# neural_network.net
KiCad netlist of a schematic drawn in EAGLE
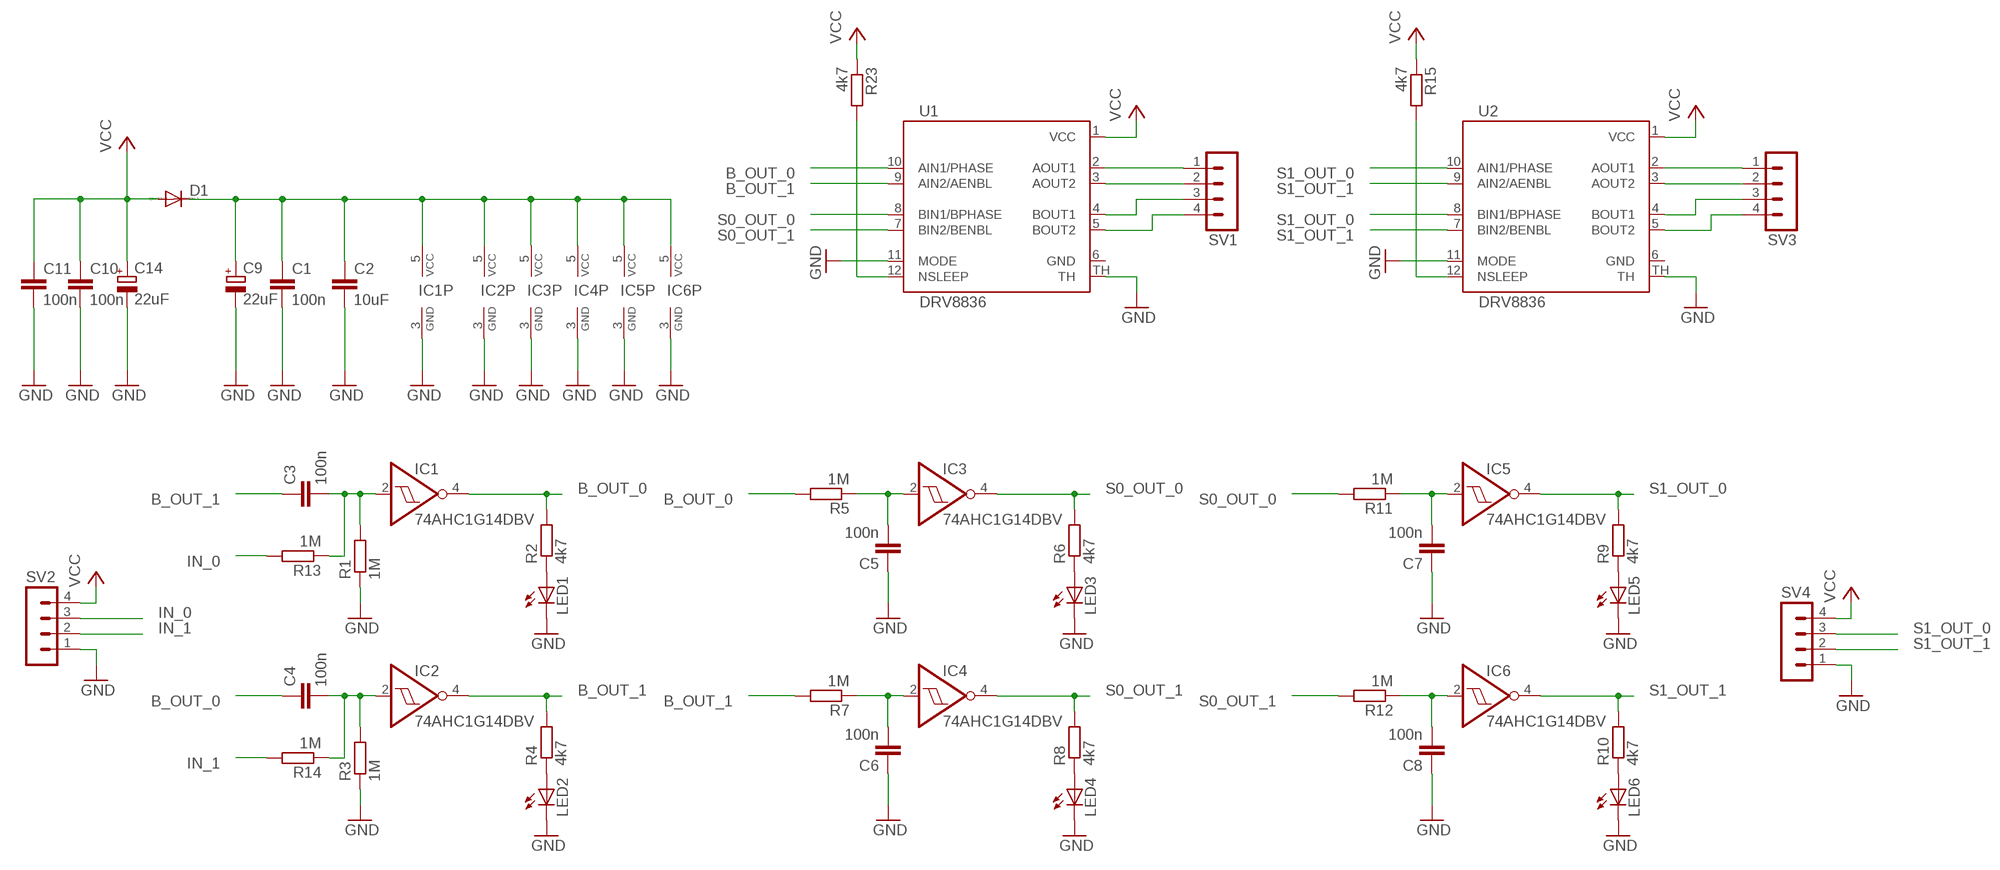
[diagram p0: schematic, sheet 1]

(export (version "E")
  (design (tool "Eeschema 10.0.6"))
  (components
    (comp (ref "C1")
      (value "100n")
      (footprint "eagle-import:C0805")
      (libsource (lib "eagle-import") (part "C-EUC0805"))
    )
    (comp (ref "C2")
      (value "10uF")
      (footprint "eagle-import:C0805")
      (libsource (lib "eagle-import") (part "C-EUC0805"))
    )
    (comp (ref "C3")
      (value "100n")
      (footprint "eagle-import:C0805")
      (libsource (lib "eagle-import") (part "C-EUC0805"))
    )
    (comp (ref "C4")
      (value "100n")
      (footprint "eagle-import:C0805")
      (libsource (lib "eagle-import") (part "C-EUC0805"))
    )
    (comp (ref "C5")
      (value "100n")
      (footprint "eagle-import:C0805")
      (libsource (lib "eagle-import") (part "C-EUC0805"))
    )
    (comp (ref "C6")
      (value "100n")
      (footprint "eagle-import:C0805")
      (libsource (lib "eagle-import") (part "C-EUC0805"))
    )
    (comp (ref "C7")
      (value "100n")
      (footprint "eagle-import:C0805")
      (libsource (lib "eagle-import") (part "C-EUC0805"))
    )
    (comp (ref "C8")
      (value "100n")
      (footprint "eagle-import:C0805")
      (libsource (lib "eagle-import") (part "C-EUC0805"))
    )
    (comp (ref "C9")
      (value "22uF")
      (footprint "eagle-import:153CLV-0605")
      (libsource (lib "eagle-import") (part "CPOL-EU153CLV-0605"))
    )
    (comp (ref "C10")
      (value "100n")
      (footprint "eagle-import:C0805")
      (libsource (lib "eagle-import") (part "C-EUC0805"))
    )
    (comp (ref "C11")
      (value "100n")
      (footprint "eagle-import:C0805")
      (libsource (lib "eagle-import") (part "C-EUC0805"))
    )
    (comp (ref "C14")
      (value "22uF")
      (footprint "eagle-import:153CLV-0605")
      (libsource (lib "eagle-import") (part "CPOL-EU153CLV-0605"))
    )
    (comp (ref "D1")
      (value "DIODE-DO214AA")
      (footprint "eagle-import:DO214AA")
      (libsource (lib "eagle-import") (part "DIODE-DO214AA"))
    )
    (comp (ref "IC1")
      (value "74AHC1G14DBV")
      (footprint "eagle-import:SOT23-5")
      (libsource (lib "eagle-import") (part "741G14DBVAHC"))
    )
    (comp (ref "IC2")
      (value "74AHC1G14DBV")
      (footprint "eagle-import:SOT23-5")
      (libsource (lib "eagle-import") (part "741G14DBVAHC"))
    )
    (comp (ref "IC3")
      (value "74AHC1G14DBV")
      (footprint "eagle-import:SOT23-5")
      (libsource (lib "eagle-import") (part "741G14DBVAHC"))
    )
    (comp (ref "IC4")
      (value "74AHC1G14DBV")
      (footprint "eagle-import:SOT23-5")
      (libsource (lib "eagle-import") (part "741G14DBVAHC"))
    )
    (comp (ref "IC5")
      (value "74AHC1G14DBV")
      (footprint "eagle-import:SOT23-5")
      (libsource (lib "eagle-import") (part "741G14DBVAHC"))
    )
    (comp (ref "IC6")
      (value "74AHC1G14DBV")
      (footprint "eagle-import:SOT23-5")
      (libsource (lib "eagle-import") (part "741G14DBVAHC"))
    )
    (comp (ref "LED1")
      (value "LEDSML1206")
      (footprint "eagle-import:SML1206")
      (libsource (lib "eagle-import") (part "LEDSML1206"))
    )
    (comp (ref "LED2")
      (value "LEDSML1206")
      (footprint "eagle-import:SML1206")
      (libsource (lib "eagle-import") (part "LEDSML1206"))
    )
    (comp (ref "LED3")
      (value "LEDSML1206")
      (footprint "eagle-import:SML1206")
      (libsource (lib "eagle-import") (part "LEDSML1206"))
    )
    (comp (ref "LED4")
      (value "LEDSML1206")
      (footprint "eagle-import:SML1206")
      (libsource (lib "eagle-import") (part "LEDSML1206"))
    )
    (comp (ref "LED5")
      (value "LEDSML1206")
      (footprint "eagle-import:SML1206")
      (libsource (lib "eagle-import") (part "LEDSML1206"))
    )
    (comp (ref "LED6")
      (value "LEDSML1206")
      (footprint "eagle-import:SML1206")
      (libsource (lib "eagle-import") (part "LEDSML1206"))
    )
    (comp (ref "R1")
      (value "1M")
      (footprint "eagle-import:M0805")
      (libsource (lib "eagle-import") (part "R-EU_M0805"))
    )
    (comp (ref "R2")
      (value "4k7")
      (footprint "eagle-import:M0805")
      (libsource (lib "eagle-import") (part "R-EU_M0805"))
    )
    (comp (ref "R3")
      (value "1M")
      (footprint "eagle-import:M0805")
      (libsource (lib "eagle-import") (part "R-EU_M0805"))
    )
    (comp (ref "R4")
      (value "4k7")
      (footprint "eagle-import:M0805")
      (libsource (lib "eagle-import") (part "R-EU_M0805"))
    )
    (comp (ref "R5")
      (value "1M")
      (footprint "eagle-import:M0805")
      (libsource (lib "eagle-import") (part "R-EU_M0805"))
    )
    (comp (ref "R6")
      (value "4k7")
      (footprint "eagle-import:M0805")
      (libsource (lib "eagle-import") (part "R-EU_M0805"))
    )
    (comp (ref "R7")
      (value "1M")
      (footprint "eagle-import:M0805")
      (libsource (lib "eagle-import") (part "R-EU_M0805"))
    )
    (comp (ref "R8")
      (value "4k7")
      (footprint "eagle-import:M0805")
      (libsource (lib "eagle-import") (part "R-EU_M0805"))
    )
    (comp (ref "R9")
      (value "4k7")
      (footprint "eagle-import:M0805")
      (libsource (lib "eagle-import") (part "R-EU_M0805"))
    )
    (comp (ref "R10")
      (value "4k7")
      (footprint "eagle-import:M0805")
      (libsource (lib "eagle-import") (part "R-EU_M0805"))
    )
    (comp (ref "R11")
      (value "1M")
      (footprint "eagle-import:M0805")
      (libsource (lib "eagle-import") (part "R-EU_M0805"))
    )
    (comp (ref "R12")
      (value "1M")
      (footprint "eagle-import:M0805")
      (libsource (lib "eagle-import") (part "R-EU_M0805"))
    )
    (comp (ref "R13")
      (value "1M")
      (footprint "eagle-import:M0805")
      (libsource (lib "eagle-import") (part "R-EU_M0805"))
    )
    (comp (ref "R14")
      (value "1M")
      (footprint "eagle-import:M0805")
      (libsource (lib "eagle-import") (part "R-EU_M0805"))
    )
    (comp (ref "R15")
      (value "4k7")
      (footprint "eagle-import:M0805")
      (libsource (lib "eagle-import") (part "R-EU_M0805"))
    )
    (comp (ref "R23")
      (value "4k7")
      (footprint "eagle-import:M0805")
      (libsource (lib "eagle-import") (part "R-EU_M0805"))
    )
    (comp (ref "SV1")
      (value "MA04-1")
      (footprint "eagle-import:MA04-1")
      (libsource (lib "eagle-import") (part "MA04-1"))
    )
    (comp (ref "SV2")
      (value "MA04-1")
      (footprint "eagle-import:MA04-1")
      (libsource (lib "eagle-import") (part "MA04-1"))
    )
    (comp (ref "SV3")
      (value "MA04-1")
      (footprint "eagle-import:MA04-1")
      (libsource (lib "eagle-import") (part "MA04-1"))
    )
    (comp (ref "SV4")
      (value "MA04-1")
      (footprint "eagle-import:MA04-1")
      (libsource (lib "eagle-import") (part "MA04-1"))
    )
    (comp (ref "U1")
      (value "DRV8836")
      (footprint "eagle-import:12WSON")
      (libsource (lib "eagle-import") (part "DRV8836"))
    )
    (comp (ref "U2")
      (value "DRV8836")
      (footprint "eagle-import:12WSON")
      (libsource (lib "eagle-import") (part "DRV8836"))
    )
  )
  (nets
    (net (code "1") (name "/B_OUT_0") (class "Default")
      (node (ref "C4") (pin "1") (pinfunction "1_1") (pintype "passive"))
      (node (ref "IC1") (pin "4") (pinfunction "O_4") (pintype "output"))
      (node (ref "R2") (pin "2") (pinfunction "2_2") (pintype "passive"))
      (node (ref "R5") (pin "2") (pinfunction "2_2") (pintype "passive"))
      (node (ref "U1") (pin "10") (pinfunction "AIN1/PHASE_10") (pintype "bidirectional"))
    )
    (net (code "2") (name "/B_OUT_1") (class "Default")
      (node (ref "C3") (pin "1") (pinfunction "1_1") (pintype "passive"))
      (node (ref "IC2") (pin "4") (pinfunction "O_4") (pintype "output"))
      (node (ref "R4") (pin "2") (pinfunction "2_2") (pintype "passive"))
      (node (ref "R7") (pin "2") (pinfunction "2_2") (pintype "passive"))
      (node (ref "U1") (pin "9") (pinfunction "AIN2/AENBL_9") (pintype "bidirectional"))
    )
    (net (code "3") (name "/IN_0") (class "Default")
      (node (ref "R13") (pin "2") (pinfunction "2_2") (pintype "passive"))
      (node (ref "SV2") (pin "3") (pinfunction "3_3") (pintype "passive"))
    )
    (net (code "4") (name "/IN_1") (class "Default")
      (node (ref "R14") (pin "2") (pinfunction "2_2") (pintype "passive"))
      (node (ref "SV2") (pin "2") (pinfunction "2_2") (pintype "passive"))
    )
    (net (code "5") (name "/S0_OUT_0") (class "Default")
      (node (ref "IC3") (pin "4") (pinfunction "O_4") (pintype "output"))
      (node (ref "R11") (pin "2") (pinfunction "2_2") (pintype "passive"))
      (node (ref "R6") (pin "2") (pinfunction "2_2") (pintype "passive"))
      (node (ref "U1") (pin "8") (pinfunction "BIN1/BPHASE_8") (pintype "bidirectional"))
    )
    (net (code "6") (name "/S0_OUT_1") (class "Default")
      (node (ref "IC4") (pin "4") (pinfunction "O_4") (pintype "output"))
      (node (ref "R12") (pin "2") (pinfunction "2_2") (pintype "passive"))
      (node (ref "R8") (pin "2") (pinfunction "2_2") (pintype "passive"))
      (node (ref "U1") (pin "7") (pinfunction "BIN2/BENBL_7") (pintype "bidirectional"))
    )
    (net (code "7") (name "/S1_OUT_0") (class "Default")
      (node (ref "IC5") (pin "4") (pinfunction "O_4") (pintype "output"))
      (node (ref "R9") (pin "2") (pinfunction "2_2") (pintype "passive"))
      (node (ref "SV4") (pin "3") (pinfunction "3_3") (pintype "passive"))
      (node (ref "U2") (pin "10") (pinfunction "AIN1/PHASE_10") (pintype "bidirectional"))
      (node (ref "U2") (pin "8") (pinfunction "BIN1/BPHASE_8") (pintype "bidirectional"))
    )
    (net (code "8") (name "/S1_OUT_1") (class "Default")
      (node (ref "IC6") (pin "4") (pinfunction "O_4") (pintype "output"))
      (node (ref "R10") (pin "2") (pinfunction "2_2") (pintype "passive"))
      (node (ref "SV4") (pin "2") (pinfunction "2_2") (pintype "passive"))
      (node (ref "U2") (pin "7") (pinfunction "BIN2/BENBL_7") (pintype "bidirectional"))
      (node (ref "U2") (pin "9") (pinfunction "AIN2/AENBL_9") (pintype "bidirectional"))
    )
    (net (code "9") (name "GND") (class "Default")
      (node (ref "C1") (pin "2") (pinfunction "2_2") (pintype "passive"))
      (node (ref "C10") (pin "2") (pinfunction "2_2") (pintype "passive"))
      (node (ref "C11") (pin "2") (pinfunction "2_2") (pintype "passive"))
      (node (ref "C14") (pin "-") (pinfunction "-_-") (pintype "passive"))
      (node (ref "C2") (pin "2") (pinfunction "2_2") (pintype "passive"))
      (node (ref "C5") (pin "1") (pinfunction "1_1") (pintype "passive"))
      (node (ref "C6") (pin "1") (pinfunction "1_1") (pintype "passive"))
      (node (ref "C7") (pin "1") (pinfunction "1_1") (pintype "passive"))
      (node (ref "C8") (pin "1") (pinfunction "1_1") (pintype "passive"))
      (node (ref "C9") (pin "-") (pinfunction "-_-") (pintype "passive"))
      (node (ref "IC1") (pin "3") (pinfunction "GND_3") (pintype "power_in"))
      (node (ref "IC2") (pin "3") (pinfunction "GND_3") (pintype "power_in"))
      (node (ref "IC3") (pin "3") (pinfunction "GND_3") (pintype "power_in"))
      (node (ref "IC4") (pin "3") (pinfunction "GND_3") (pintype "power_in"))
      (node (ref "IC5") (pin "3") (pinfunction "GND_3") (pintype "power_in"))
      (node (ref "IC6") (pin "3") (pinfunction "GND_3") (pintype "power_in"))
      (node (ref "LED1") (pin "C") (pinfunction "C_C") (pintype "passive"))
      (node (ref "LED2") (pin "C") (pinfunction "C_C") (pintype "passive"))
      (node (ref "LED3") (pin "C") (pinfunction "C_C") (pintype "passive"))
      (node (ref "LED4") (pin "C") (pinfunction "C_C") (pintype "passive"))
      (node (ref "LED5") (pin "C") (pinfunction "C_C") (pintype "passive"))
      (node (ref "LED6") (pin "C") (pinfunction "C_C") (pintype "passive"))
      (node (ref "R1") (pin "1") (pinfunction "1_1") (pintype "passive"))
      (node (ref "R3") (pin "1") (pinfunction "1_1") (pintype "passive"))
      (node (ref "SV2") (pin "1") (pinfunction "1_1") (pintype "passive"))
      (node (ref "SV4") (pin "1") (pinfunction "1_1") (pintype "passive"))
      (node (ref "U1") (pin "11") (pinfunction "MODE_11") (pintype "bidirectional"))
      (node (ref "U1") (pin "TH") (pinfunction "TH_TH") (pintype "bidirectional"))
      (node (ref "U2") (pin "11") (pinfunction "MODE_11") (pintype "bidirectional"))
      (node (ref "U2") (pin "TH") (pinfunction "TH_TH") (pintype "bidirectional"))
    )
    (net (code "10") (name "Net-(IC1A-I)") (class "Default")
      (node (ref "C3") (pin "2") (pinfunction "2_2") (pintype "passive"))
      (node (ref "IC1") (pin "2") (pinfunction "I_2") (pintype "input"))
      (node (ref "R1") (pin "2") (pinfunction "2_2") (pintype "passive"))
      (node (ref "R13") (pin "1") (pinfunction "1_1") (pintype "passive"))
    )
    (net (code "11") (name "Net-(IC1B-VCC)") (class "Default")
      (node (ref "C1") (pin "1") (pinfunction "1_1") (pintype "passive"))
      (node (ref "C2") (pin "1") (pinfunction "1_1") (pintype "passive"))
      (node (ref "C9") (pin "+") (pinfunction "+_+") (pintype "passive"))
      (node (ref "D1") (pin "C") (pinfunction "C_C") (pintype "passive"))
      (node (ref "IC1") (pin "5") (pinfunction "VCC_5") (pintype "power_in"))
      (node (ref "IC2") (pin "5") (pinfunction "VCC_5") (pintype "power_in"))
      (node (ref "IC3") (pin "5") (pinfunction "VCC_5") (pintype "power_in"))
      (node (ref "IC4") (pin "5") (pinfunction "VCC_5") (pintype "power_in"))
      (node (ref "IC5") (pin "5") (pinfunction "VCC_5") (pintype "power_in"))
      (node (ref "IC6") (pin "5") (pinfunction "VCC_5") (pintype "power_in"))
    )
    (net (code "12") (name "Net-(IC2A-I)") (class "Default")
      (node (ref "C4") (pin "2") (pinfunction "2_2") (pintype "passive"))
      (node (ref "IC2") (pin "2") (pinfunction "I_2") (pintype "input"))
      (node (ref "R14") (pin "1") (pinfunction "1_1") (pintype "passive"))
      (node (ref "R3") (pin "2") (pinfunction "2_2") (pintype "passive"))
    )
    (net (code "13") (name "Net-(IC3A-I)") (class "Default")
      (node (ref "C5") (pin "2") (pinfunction "2_2") (pintype "passive"))
      (node (ref "IC3") (pin "2") (pinfunction "I_2") (pintype "input"))
      (node (ref "R5") (pin "1") (pinfunction "1_1") (pintype "passive"))
    )
    (net (code "14") (name "Net-(IC4A-I)") (class "Default")
      (node (ref "C6") (pin "2") (pinfunction "2_2") (pintype "passive"))
      (node (ref "IC4") (pin "2") (pinfunction "I_2") (pintype "input"))
      (node (ref "R7") (pin "1") (pinfunction "1_1") (pintype "passive"))
    )
    (net (code "15") (name "Net-(IC5A-I)") (class "Default")
      (node (ref "C7") (pin "2") (pinfunction "2_2") (pintype "passive"))
      (node (ref "IC5") (pin "2") (pinfunction "I_2") (pintype "input"))
      (node (ref "R11") (pin "1") (pinfunction "1_1") (pintype "passive"))
    )
    (net (code "16") (name "Net-(IC6A-I)") (class "Default")
      (node (ref "C8") (pin "2") (pinfunction "2_2") (pintype "passive"))
      (node (ref "IC6") (pin "2") (pinfunction "I_2") (pintype "input"))
      (node (ref "R12") (pin "1") (pinfunction "1_1") (pintype "passive"))
    )
    (net (code "17") (name "Net-(LED1-PadA)") (class "Default")
      (node (ref "LED1") (pin "A") (pinfunction "A_A") (pintype "passive"))
      (node (ref "R2") (pin "1") (pinfunction "1_1") (pintype "passive"))
    )
    (net (code "18") (name "Net-(LED2-PadA)") (class "Default")
      (node (ref "LED2") (pin "A") (pinfunction "A_A") (pintype "passive"))
      (node (ref "R4") (pin "1") (pinfunction "1_1") (pintype "passive"))
    )
    (net (code "19") (name "Net-(LED3-PadA)") (class "Default")
      (node (ref "LED3") (pin "A") (pinfunction "A_A") (pintype "passive"))
      (node (ref "R6") (pin "1") (pinfunction "1_1") (pintype "passive"))
    )
    (net (code "20") (name "Net-(LED4-PadA)") (class "Default")
      (node (ref "LED4") (pin "A") (pinfunction "A_A") (pintype "passive"))
      (node (ref "R8") (pin "1") (pinfunction "1_1") (pintype "passive"))
    )
    (net (code "21") (name "Net-(LED5-PadA)") (class "Default")
      (node (ref "LED5") (pin "A") (pinfunction "A_A") (pintype "passive"))
      (node (ref "R9") (pin "1") (pinfunction "1_1") (pintype "passive"))
    )
    (net (code "22") (name "Net-(LED6-PadA)") (class "Default")
      (node (ref "LED6") (pin "A") (pinfunction "A_A") (pintype "passive"))
      (node (ref "R10") (pin "1") (pinfunction "1_1") (pintype "passive"))
    )
    (net (code "23") (name "Net-(U1-AOUT1)") (class "Default")
      (node (ref "SV1") (pin "1") (pinfunction "1_1") (pintype "passive"))
      (node (ref "U1") (pin "2") (pinfunction "AOUT1_2") (pintype "bidirectional"))
    )
    (net (code "24") (name "Net-(U1-AOUT2)") (class "Default")
      (node (ref "SV1") (pin "2") (pinfunction "2_2") (pintype "passive"))
      (node (ref "U1") (pin "3") (pinfunction "AOUT2_3") (pintype "bidirectional"))
    )
    (net (code "25") (name "Net-(U1-BOUT1)") (class "Default")
      (node (ref "SV1") (pin "3") (pinfunction "3_3") (pintype "passive"))
      (node (ref "U1") (pin "4") (pinfunction "BOUT1_4") (pintype "bidirectional"))
    )
    (net (code "26") (name "Net-(U1-BOUT2)") (class "Default")
      (node (ref "SV1") (pin "4") (pinfunction "4_4") (pintype "passive"))
      (node (ref "U1") (pin "5") (pinfunction "BOUT2_5") (pintype "bidirectional"))
    )
    (net (code "27") (name "Net-(U1-NSLEEP)") (class "Default")
      (node (ref "R23") (pin "2") (pinfunction "2_2") (pintype "passive"))
      (node (ref "U1") (pin "12") (pinfunction "NSLEEP_12") (pintype "bidirectional"))
    )
    (net (code "28") (name "Net-(U2-AOUT1)") (class "Default")
      (node (ref "SV3") (pin "1") (pinfunction "1_1") (pintype "passive"))
      (node (ref "U2") (pin "2") (pinfunction "AOUT1_2") (pintype "bidirectional"))
    )
    (net (code "29") (name "Net-(U2-AOUT2)") (class "Default")
      (node (ref "SV3") (pin "2") (pinfunction "2_2") (pintype "passive"))
      (node (ref "U2") (pin "3") (pinfunction "AOUT2_3") (pintype "bidirectional"))
    )
    (net (code "30") (name "Net-(U2-BOUT1)") (class "Default")
      (node (ref "SV3") (pin "3") (pinfunction "3_3") (pintype "passive"))
      (node (ref "U2") (pin "4") (pinfunction "BOUT1_4") (pintype "bidirectional"))
    )
    (net (code "31") (name "Net-(U2-BOUT2)") (class "Default")
      (node (ref "SV3") (pin "4") (pinfunction "4_4") (pintype "passive"))
      (node (ref "U2") (pin "5") (pinfunction "BOUT2_5") (pintype "bidirectional"))
    )
    (net (code "32") (name "Net-(U2-NSLEEP)") (class "Default")
      (node (ref "R15") (pin "2") (pinfunction "2_2") (pintype "passive"))
      (node (ref "U2") (pin "12") (pinfunction "NSLEEP_12") (pintype "bidirectional"))
    )
    (net (code "33") (name "VCC") (class "Default")
      (node (ref "C10") (pin "1") (pinfunction "1_1") (pintype "passive"))
      (node (ref "C11") (pin "1") (pinfunction "1_1") (pintype "passive"))
      (node (ref "C14") (pin "+") (pinfunction "+_+") (pintype "passive"))
      (node (ref "D1") (pin "A") (pinfunction "A_A") (pintype "passive"))
      (node (ref "R15") (pin "1") (pinfunction "1_1") (pintype "passive"))
      (node (ref "R23") (pin "1") (pinfunction "1_1") (pintype "passive"))
      (node (ref "SV2") (pin "4") (pinfunction "4_4") (pintype "passive"))
      (node (ref "SV4") (pin "4") (pinfunction "4_4") (pintype "passive"))
      (node (ref "U1") (pin "1") (pinfunction "VCC_1") (pintype "bidirectional"))
      (node (ref "U2") (pin "1") (pinfunction "VCC_1") (pintype "bidirectional"))
    )
    (net (code "34") (name "unconnected-(U1-GND-Pad6)") (class "Default")
      (node (ref "U1") (pin "6") (pinfunction "GND_6") (pintype "bidirectional"))
    )
    (net (code "35") (name "unconnected-(U2-GND-Pad6)") (class "Default")
      (node (ref "U2") (pin "6") (pinfunction "GND_6") (pintype "bidirectional"))
    )
  )
)
